# gforce2.net
KiCad netlist of a schematic drawn in EAGLE
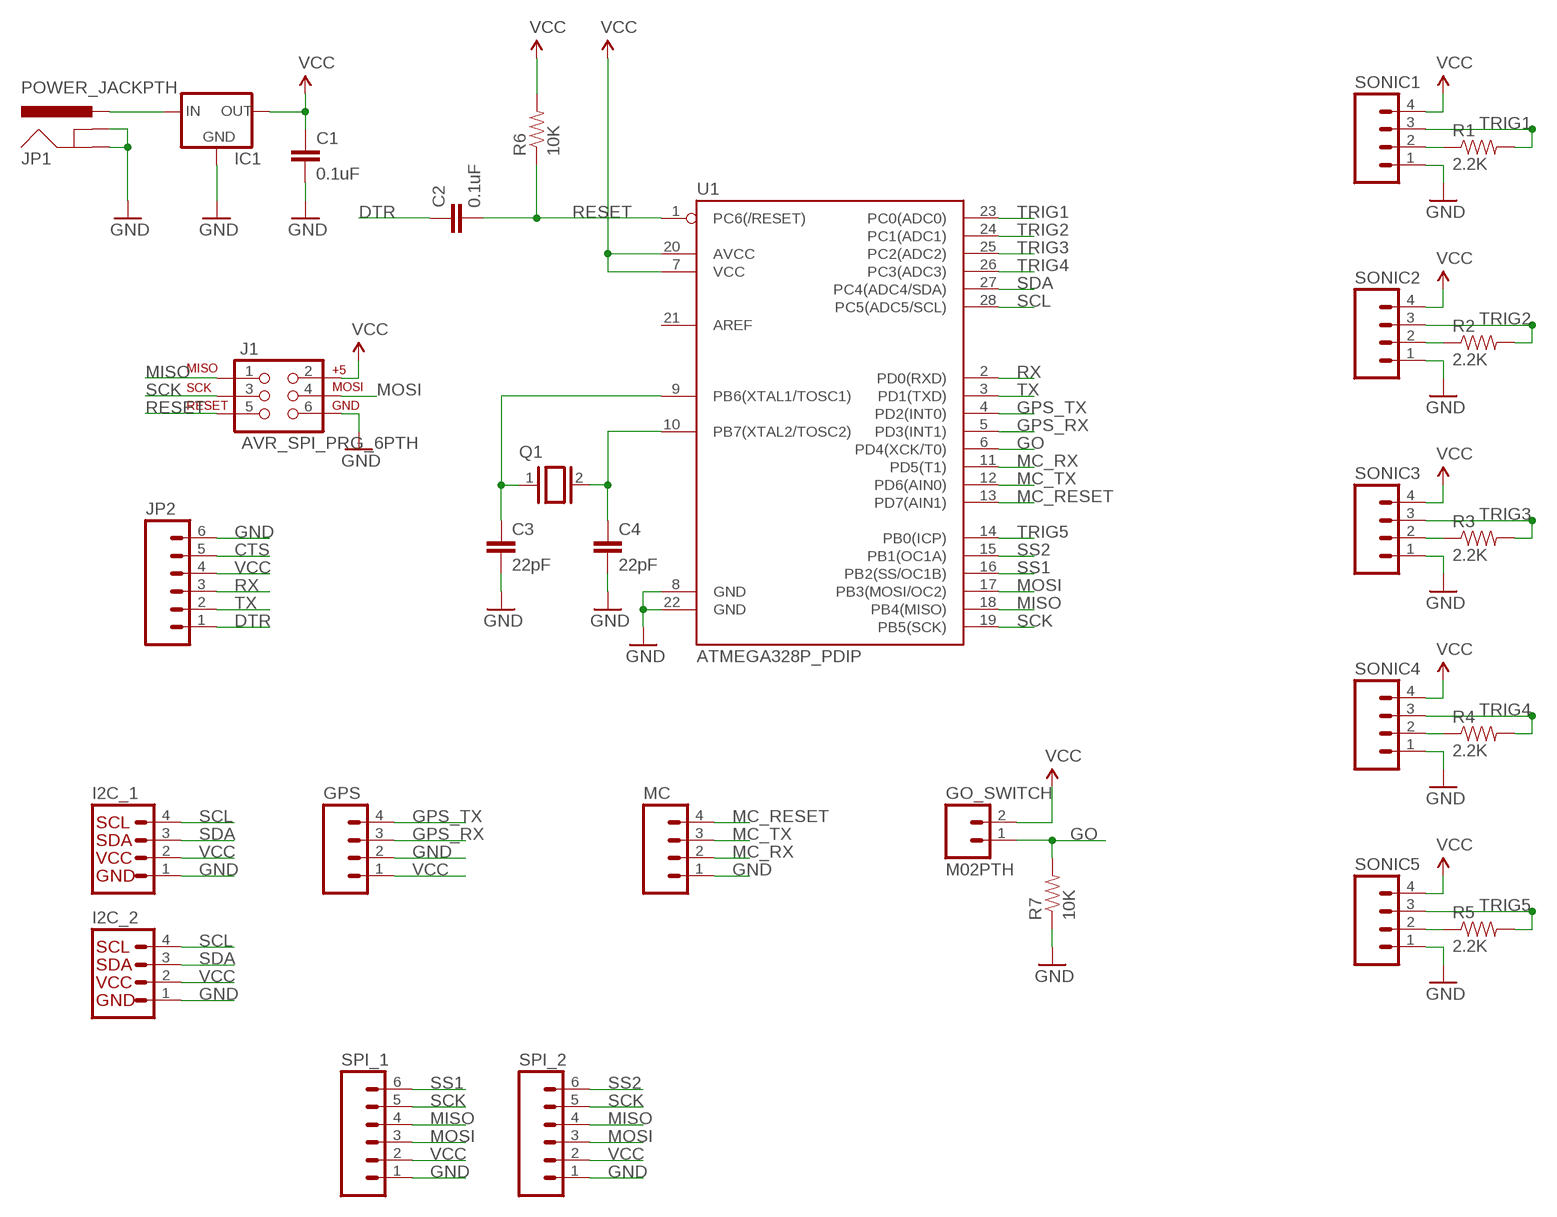
[diagram p0: schematic, sheet 1]

(export (version "E")
  (design (tool "Eeschema 10.0.6"))
  (components
    (comp (ref "C1")
      (value "0.1uF")
      (footprint "eagle-import:CAP-PTH-SMALL")
      (libsource (lib "eagle-import") (part "CAPPTH"))
    )
    (comp (ref "C2")
      (value "0.1uF")
      (footprint "eagle-import:CAP-PTH-SMALL")
      (libsource (lib "eagle-import") (part "CAPPTH"))
    )
    (comp (ref "C3")
      (value "22pF")
      (footprint "eagle-import:CAP-PTH-SMALL")
      (libsource (lib "eagle-import") (part "SparkFun-Passives_CAPPTH"))
    )
    (comp (ref "C4")
      (value "22pF")
      (footprint "eagle-import:CAP-PTH-SMALL")
      (libsource (lib "eagle-import") (part "SparkFun-Passives_CAPPTH"))
    )
    (comp (ref "GO_SWITCH")
      (value "M02PTH")
      (footprint "eagle-import:1X02")
      (libsource (lib "eagle-import") (part "M02PTH"))
    )
    (comp (ref "GPS")
      (value "M04PTH")
      (footprint "eagle-import:1X04")
      (libsource (lib "eagle-import") (part "M04PTH"))
    )
    (comp (ref "I2C_1")
      (value "I2C_STANDARD")
      (footprint "eagle-import:1X04")
      (libsource (lib "eagle-import") (part "I2C_STANDARD"))
    )
    (comp (ref "I2C_2")
      (value "I2C_STANDARD")
      (footprint "eagle-import:1X04")
      (libsource (lib "eagle-import") (part "I2C_STANDARD"))
    )
    (comp (ref "IC1")
      (value "V_REG_78XXSIDE")
      (footprint "eagle-import:78XXL")
      (libsource (lib "eagle-import") (part "V_REG_78XXSIDE"))
    )
    (comp (ref "J1")
      (value "AVR_SPI_PRG_6PTH")
      (footprint "eagle-import:2X3")
      (libsource (lib "eagle-import") (part "AVR_SPI_PRG_6PTH"))
    )
    (comp (ref "JP1")
      (value "POWER_JACKPTH")
      (footprint "eagle-import:POWER_JACK_PTH")
      (libsource (lib "eagle-import") (part "POWER_JACKPTH"))
    )
    (comp (ref "JP2")
      (value "M06SILK_FEMALE_PTH")
      (footprint "eagle-import:1X06")
      (libsource (lib "eagle-import") (part "M06SILK_FEMALE_PTH"))
    )
    (comp (ref "MC")
      (value "M04PTH")
      (footprint "eagle-import:1X04")
      (libsource (lib "eagle-import") (part "M04PTH"))
    )
    (comp (ref "Q1")
      (value "XTAL/S")
      (footprint "eagle-import:QS")
      (libsource (lib "eagle-import") (part "XTAL/S"))
    )
    (comp (ref "R1")
      (value "2.2K")
      (footprint "eagle-import:AXIAL-0.4")
      (libsource (lib "eagle-import") (part "RESISTORPTH-1/4W"))
    )
    (comp (ref "R2")
      (value "2.2K")
      (footprint "eagle-import:AXIAL-0.4")
      (libsource (lib "eagle-import") (part "RESISTORPTH-1/4W"))
    )
    (comp (ref "R3")
      (value "2.2K")
      (footprint "eagle-import:AXIAL-0.4")
      (libsource (lib "eagle-import") (part "RESISTORPTH-1/4W"))
    )
    (comp (ref "R4")
      (value "2.2K")
      (footprint "eagle-import:AXIAL-0.4")
      (libsource (lib "eagle-import") (part "RESISTORPTH-1/4W"))
    )
    (comp (ref "R5")
      (value "2.2K")
      (footprint "eagle-import:AXIAL-0.4")
      (libsource (lib "eagle-import") (part "RESISTORPTH-1/4W"))
    )
    (comp (ref "R6")
      (value "10K")
      (footprint "eagle-import:AXIAL-0.4")
      (libsource (lib "eagle-import") (part "RESISTORPTH-1/4W"))
    )
    (comp (ref "R7")
      (value "10K")
      (footprint "eagle-import:AXIAL-0.4")
      (libsource (lib "eagle-import") (part "RESISTORPTH-1/4W"))
    )
    (comp (ref "SONIC1")
      (value "M04PTH")
      (footprint "eagle-import:1X04")
      (libsource (lib "eagle-import") (part "M04PTH"))
    )
    (comp (ref "SONIC2")
      (value "M04PTH")
      (footprint "eagle-import:1X04")
      (libsource (lib "eagle-import") (part "M04PTH"))
    )
    (comp (ref "SONIC3")
      (value "M04PTH")
      (footprint "eagle-import:1X04")
      (libsource (lib "eagle-import") (part "M04PTH"))
    )
    (comp (ref "SONIC4")
      (value "M04PTH")
      (footprint "eagle-import:1X04")
      (libsource (lib "eagle-import") (part "M04PTH"))
    )
    (comp (ref "SONIC5")
      (value "M04PTH")
      (footprint "eagle-import:1X04")
      (libsource (lib "eagle-import") (part "M04PTH"))
    )
    (comp (ref "SPI_1")
      (value "M06SILK_FEMALE_PTH")
      (footprint "eagle-import:1X06")
      (libsource (lib "eagle-import") (part "M06SILK_FEMALE_PTH"))
    )
    (comp (ref "SPI_2")
      (value "M06SILK_FEMALE_PTH")
      (footprint "eagle-import:1X06")
      (libsource (lib "eagle-import") (part "M06SILK_FEMALE_PTH"))
    )
    (comp (ref "U1")
      (value "ATMEGA328P_PDIP")
      (footprint "eagle-import:DIL28-3")
      (libsource (lib "eagle-import") (part "ATMEGA328P_PDIP"))
    )
  )
  (nets
    (net (code "1") (name "/CTS") (class "Default")
      (node (ref "JP2") (pin "5") (pinfunction "5_5") (pintype "passive"))
    )
    (net (code "2") (name "/DTR") (class "Default")
      (node (ref "C2") (pin "1") (pinfunction "1_1") (pintype "passive"))
      (node (ref "JP2") (pin "1") (pinfunction "1_1") (pintype "passive"))
    )
    (net (code "3") (name "/GO") (class "Default")
      (node (ref "GO_SWITCH") (pin "1") (pinfunction "1_1") (pintype "passive"))
      (node (ref "R7") (pin "P$2") (pinfunction "2_P$2") (pintype "passive"))
      (node (ref "U1") (pin "6") (pinfunction "PD4(XCK/T0)_6") (pintype "bidirectional"))
    )
    (net (code "4") (name "/GPS_RX") (class "Default")
      (node (ref "GPS") (pin "3") (pinfunction "3_3") (pintype "passive"))
      (node (ref "U1") (pin "5") (pinfunction "PD3(INT1)_5") (pintype "bidirectional"))
    )
    (net (code "5") (name "/GPS_TX") (class "Default")
      (node (ref "GPS") (pin "4") (pinfunction "4_4") (pintype "passive"))
      (node (ref "U1") (pin "4") (pinfunction "PD2(INT0)_4") (pintype "bidirectional"))
    )
    (net (code "6") (name "/MC_RESET") (class "Default")
      (node (ref "MC") (pin "4") (pinfunction "4_4") (pintype "passive"))
      (node (ref "U1") (pin "13") (pinfunction "PD7(AIN1)_13") (pintype "bidirectional"))
    )
    (net (code "7") (name "/MC_RX") (class "Default")
      (node (ref "MC") (pin "2") (pinfunction "2_2") (pintype "passive"))
      (node (ref "U1") (pin "11") (pinfunction "PD5(T1)_11") (pintype "bidirectional"))
    )
    (net (code "8") (name "/MC_TX") (class "Default")
      (node (ref "MC") (pin "3") (pinfunction "3_3") (pintype "passive"))
      (node (ref "U1") (pin "12") (pinfunction "PD6(AIN0)_12") (pintype "bidirectional"))
    )
    (net (code "9") (name "/MISO") (class "Default")
      (node (ref "J1") (pin "1") (pinfunction "1_1") (pintype "passive"))
      (node (ref "SPI_1") (pin "4") (pinfunction "4_4") (pintype "passive"))
      (node (ref "SPI_2") (pin "4") (pinfunction "4_4") (pintype "passive"))
      (node (ref "U1") (pin "18") (pinfunction "PB4(MISO)_18") (pintype "bidirectional"))
    )
    (net (code "10") (name "/MOSI") (class "Default")
      (node (ref "J1") (pin "4") (pinfunction "4_4") (pintype "passive"))
      (node (ref "SPI_1") (pin "3") (pinfunction "3_3") (pintype "passive"))
      (node (ref "SPI_2") (pin "3") (pinfunction "3_3") (pintype "passive"))
      (node (ref "U1") (pin "17") (pinfunction "PB3(MOSI/OC2)_17") (pintype "bidirectional"))
    )
    (net (code "11") (name "/RESET") (class "Default")
      (node (ref "C2") (pin "2") (pinfunction "2_2") (pintype "passive"))
      (node (ref "J1") (pin "5") (pinfunction "5_5") (pintype "passive"))
      (node (ref "R6") (pin "P$1") (pinfunction "1_P$1") (pintype "passive"))
      (node (ref "U1") (pin "1") (pinfunction "PC6(/RESET)_1") (pintype "bidirectional"))
    )
    (net (code "12") (name "/RX") (class "Default")
      (node (ref "JP2") (pin "3") (pinfunction "3_3") (pintype "passive"))
      (node (ref "U1") (pin "2") (pinfunction "PD0(RXD)_2") (pintype "bidirectional"))
    )
    (net (code "13") (name "/SCK") (class "Default")
      (node (ref "J1") (pin "3") (pinfunction "3_3") (pintype "passive"))
      (node (ref "SPI_1") (pin "5") (pinfunction "5_5") (pintype "passive"))
      (node (ref "SPI_2") (pin "5") (pinfunction "5_5") (pintype "passive"))
      (node (ref "U1") (pin "19") (pinfunction "PB5(SCK)_19") (pintype "bidirectional"))
    )
    (net (code "14") (name "/SCL") (class "Default")
      (node (ref "I2C_1") (pin "4") (pinfunction "4_4") (pintype "passive"))
      (node (ref "I2C_2") (pin "4") (pinfunction "4_4") (pintype "passive"))
      (node (ref "U1") (pin "28") (pinfunction "PC5(ADC5/SCL)_28") (pintype "bidirectional"))
    )
    (net (code "15") (name "/SDA") (class "Default")
      (node (ref "I2C_1") (pin "3") (pinfunction "3_3") (pintype "passive"))
      (node (ref "I2C_2") (pin "3") (pinfunction "3_3") (pintype "passive"))
      (node (ref "U1") (pin "27") (pinfunction "PC4(ADC4/SDA)_27") (pintype "bidirectional"))
    )
    (net (code "16") (name "/SS1") (class "Default")
      (node (ref "SPI_1") (pin "6") (pinfunction "6_6") (pintype "passive"))
      (node (ref "U1") (pin "16") (pinfunction "PB2(SS/OC1B)_16") (pintype "bidirectional"))
    )
    (net (code "17") (name "/SS2") (class "Default")
      (node (ref "SPI_2") (pin "6") (pinfunction "6_6") (pintype "passive"))
      (node (ref "U1") (pin "15") (pinfunction "PB1(OC1A)_15") (pintype "bidirectional"))
    )
    (net (code "18") (name "/TRIG1") (class "Default")
      (node (ref "R1") (pin "P$2") (pinfunction "2_P$2") (pintype "passive"))
      (node (ref "SONIC1") (pin "3") (pinfunction "3_3") (pintype "passive"))
      (node (ref "U1") (pin "23") (pinfunction "PC0(ADC0)_23") (pintype "bidirectional"))
    )
    (net (code "19") (name "/TRIG2") (class "Default")
      (node (ref "R2") (pin "P$2") (pinfunction "2_P$2") (pintype "passive"))
      (node (ref "SONIC2") (pin "3") (pinfunction "3_3") (pintype "passive"))
      (node (ref "U1") (pin "24") (pinfunction "PC1(ADC1)_24") (pintype "bidirectional"))
    )
    (net (code "20") (name "/TRIG3") (class "Default")
      (node (ref "R3") (pin "P$2") (pinfunction "2_P$2") (pintype "passive"))
      (node (ref "SONIC3") (pin "3") (pinfunction "3_3") (pintype "passive"))
      (node (ref "U1") (pin "25") (pinfunction "PC2(ADC2)_25") (pintype "bidirectional"))
    )
    (net (code "21") (name "/TRIG4") (class "Default")
      (node (ref "R4") (pin "P$2") (pinfunction "2_P$2") (pintype "passive"))
      (node (ref "SONIC4") (pin "3") (pinfunction "3_3") (pintype "passive"))
      (node (ref "U1") (pin "26") (pinfunction "PC3(ADC3)_26") (pintype "bidirectional"))
    )
    (net (code "22") (name "/TRIG5") (class "Default")
      (node (ref "R5") (pin "P$2") (pinfunction "2_P$2") (pintype "passive"))
      (node (ref "SONIC5") (pin "3") (pinfunction "3_3") (pintype "passive"))
      (node (ref "U1") (pin "14") (pinfunction "PB0(ICP)_14") (pintype "bidirectional"))
    )
    (net (code "23") (name "/TX") (class "Default")
      (node (ref "JP2") (pin "2") (pinfunction "2_2") (pintype "passive"))
      (node (ref "U1") (pin "3") (pinfunction "PD1(TXD)_3") (pintype "bidirectional"))
    )
    (net (code "24") (name "GND") (class "Default")
      (node (ref "C1") (pin "2") (pinfunction "2_2") (pintype "passive"))
      (node (ref "C3") (pin "2") (pinfunction "2_2") (pintype "passive"))
      (node (ref "C4") (pin "2") (pinfunction "2_2") (pintype "passive"))
      (node (ref "GPS") (pin "2") (pinfunction "2_2") (pintype "passive"))
      (node (ref "I2C_1") (pin "1") (pinfunction "1_1") (pintype "passive"))
      (node (ref "I2C_2") (pin "1") (pinfunction "1_1") (pintype "passive"))
      (node (ref "IC1") (pin "GND") (pinfunction "GND_GND") (pintype "input"))
      (node (ref "J1") (pin "6") (pinfunction "6_6") (pintype "passive"))
      (node (ref "JP1") (pin "GND") (pinfunction "GND_GND") (pintype "bidirectional"))
      (node (ref "JP1") (pin "GNDBREAK") (pinfunction "GNDBREAK_GNDBREAK") (pintype "bidirectional"))
      (node (ref "JP2") (pin "6") (pinfunction "6_6") (pintype "passive"))
      (node (ref "MC") (pin "1") (pinfunction "1_1") (pintype "passive"))
      (node (ref "R7") (pin "P$1") (pinfunction "1_P$1") (pintype "passive"))
      (node (ref "SONIC1") (pin "1") (pinfunction "1_1") (pintype "passive"))
      (node (ref "SONIC2") (pin "1") (pinfunction "1_1") (pintype "passive"))
      (node (ref "SONIC3") (pin "1") (pinfunction "1_1") (pintype "passive"))
      (node (ref "SONIC4") (pin "1") (pinfunction "1_1") (pintype "passive"))
      (node (ref "SONIC5") (pin "1") (pinfunction "1_1") (pintype "passive"))
      (node (ref "SPI_1") (pin "1") (pinfunction "1_1") (pintype "passive"))
      (node (ref "SPI_2") (pin "1") (pinfunction "1_1") (pintype "passive"))
      (node (ref "U1") (pin "22") (pinfunction "GND_22") (pintype "bidirectional"))
      (node (ref "U1") (pin "8") (pinfunction "GND_8") (pintype "bidirectional"))
    )
    (net (code "25") (name "Net-(IC1-PadIN)") (class "Default")
      (node (ref "IC1") (pin "IN") (pinfunction "IN_IN") (pintype "input"))
      (node (ref "JP1") (pin "PWR") (pinfunction "PWR_PWR") (pintype "bidirectional"))
    )
    (net (code "26") (name "Net-(R1-1)") (class "Default")
      (node (ref "R1") (pin "P$1") (pinfunction "1_P$1") (pintype "passive"))
      (node (ref "SONIC1") (pin "2") (pinfunction "2_2") (pintype "passive"))
    )
    (net (code "27") (name "Net-(R2-1)") (class "Default")
      (node (ref "R2") (pin "P$1") (pinfunction "1_P$1") (pintype "passive"))
      (node (ref "SONIC2") (pin "2") (pinfunction "2_2") (pintype "passive"))
    )
    (net (code "28") (name "Net-(R3-1)") (class "Default")
      (node (ref "R3") (pin "P$1") (pinfunction "1_P$1") (pintype "passive"))
      (node (ref "SONIC3") (pin "2") (pinfunction "2_2") (pintype "passive"))
    )
    (net (code "29") (name "Net-(R4-1)") (class "Default")
      (node (ref "R4") (pin "P$1") (pinfunction "1_P$1") (pintype "passive"))
      (node (ref "SONIC4") (pin "2") (pinfunction "2_2") (pintype "passive"))
    )
    (net (code "30") (name "Net-(R5-1)") (class "Default")
      (node (ref "R5") (pin "P$1") (pinfunction "1_P$1") (pintype "passive"))
      (node (ref "SONIC5") (pin "2") (pinfunction "2_2") (pintype "passive"))
    )
    (net (code "31") (name "Net-(U1-PB6(XTAL1{slash}TOSC1))") (class "Default")
      (node (ref "C3") (pin "1") (pinfunction "1_1") (pintype "passive"))
      (node (ref "Q1") (pin "1") (pinfunction "1_1") (pintype "passive"))
      (node (ref "U1") (pin "9") (pinfunction "PB6(XTAL1/TOSC1)_9") (pintype "bidirectional"))
    )
    (net (code "32") (name "Net-(U1-PB7(XTAL2{slash}TOSC2))") (class "Default")
      (node (ref "C4") (pin "1") (pinfunction "1_1") (pintype "passive"))
      (node (ref "Q1") (pin "2") (pinfunction "2_2") (pintype "passive"))
      (node (ref "U1") (pin "10") (pinfunction "PB7(XTAL2/TOSC2)_10") (pintype "bidirectional"))
    )
    (net (code "33") (name "VCC") (class "Default")
      (node (ref "C1") (pin "1") (pinfunction "1_1") (pintype "passive"))
      (node (ref "GO_SWITCH") (pin "2") (pinfunction "2_2") (pintype "passive"))
      (node (ref "GPS") (pin "1") (pinfunction "1_1") (pintype "passive"))
      (node (ref "I2C_1") (pin "2") (pinfunction "2_2") (pintype "passive"))
      (node (ref "I2C_2") (pin "2") (pinfunction "2_2") (pintype "passive"))
      (node (ref "IC1") (pin "OUT") (pinfunction "OUT_OUT") (pintype "output"))
      (node (ref "J1") (pin "2") (pinfunction "2_2") (pintype "passive"))
      (node (ref "JP2") (pin "4") (pinfunction "4_4") (pintype "passive"))
      (node (ref "R6") (pin "P$2") (pinfunction "2_P$2") (pintype "passive"))
      (node (ref "SONIC1") (pin "4") (pinfunction "4_4") (pintype "passive"))
      (node (ref "SONIC2") (pin "4") (pinfunction "4_4") (pintype "passive"))
      (node (ref "SONIC3") (pin "4") (pinfunction "4_4") (pintype "passive"))
      (node (ref "SONIC4") (pin "4") (pinfunction "4_4") (pintype "passive"))
      (node (ref "SONIC5") (pin "4") (pinfunction "4_4") (pintype "passive"))
      (node (ref "SPI_1") (pin "2") (pinfunction "2_2") (pintype "passive"))
      (node (ref "SPI_2") (pin "2") (pinfunction "2_2") (pintype "passive"))
      (node (ref "U1") (pin "20") (pinfunction "AVCC_20") (pintype "bidirectional"))
      (node (ref "U1") (pin "7") (pinfunction "VCC_7") (pintype "bidirectional"))
    )
    (net (code "34") (name "unconnected-(U1-AREF-Pad21)") (class "Default")
      (node (ref "U1") (pin "21") (pinfunction "AREF_21") (pintype "bidirectional"))
    )
  )
)
